# 09_-_MICROCONTROLLER_UNIT.net
KiCad netlist of a schematic drawn in Altium Designer
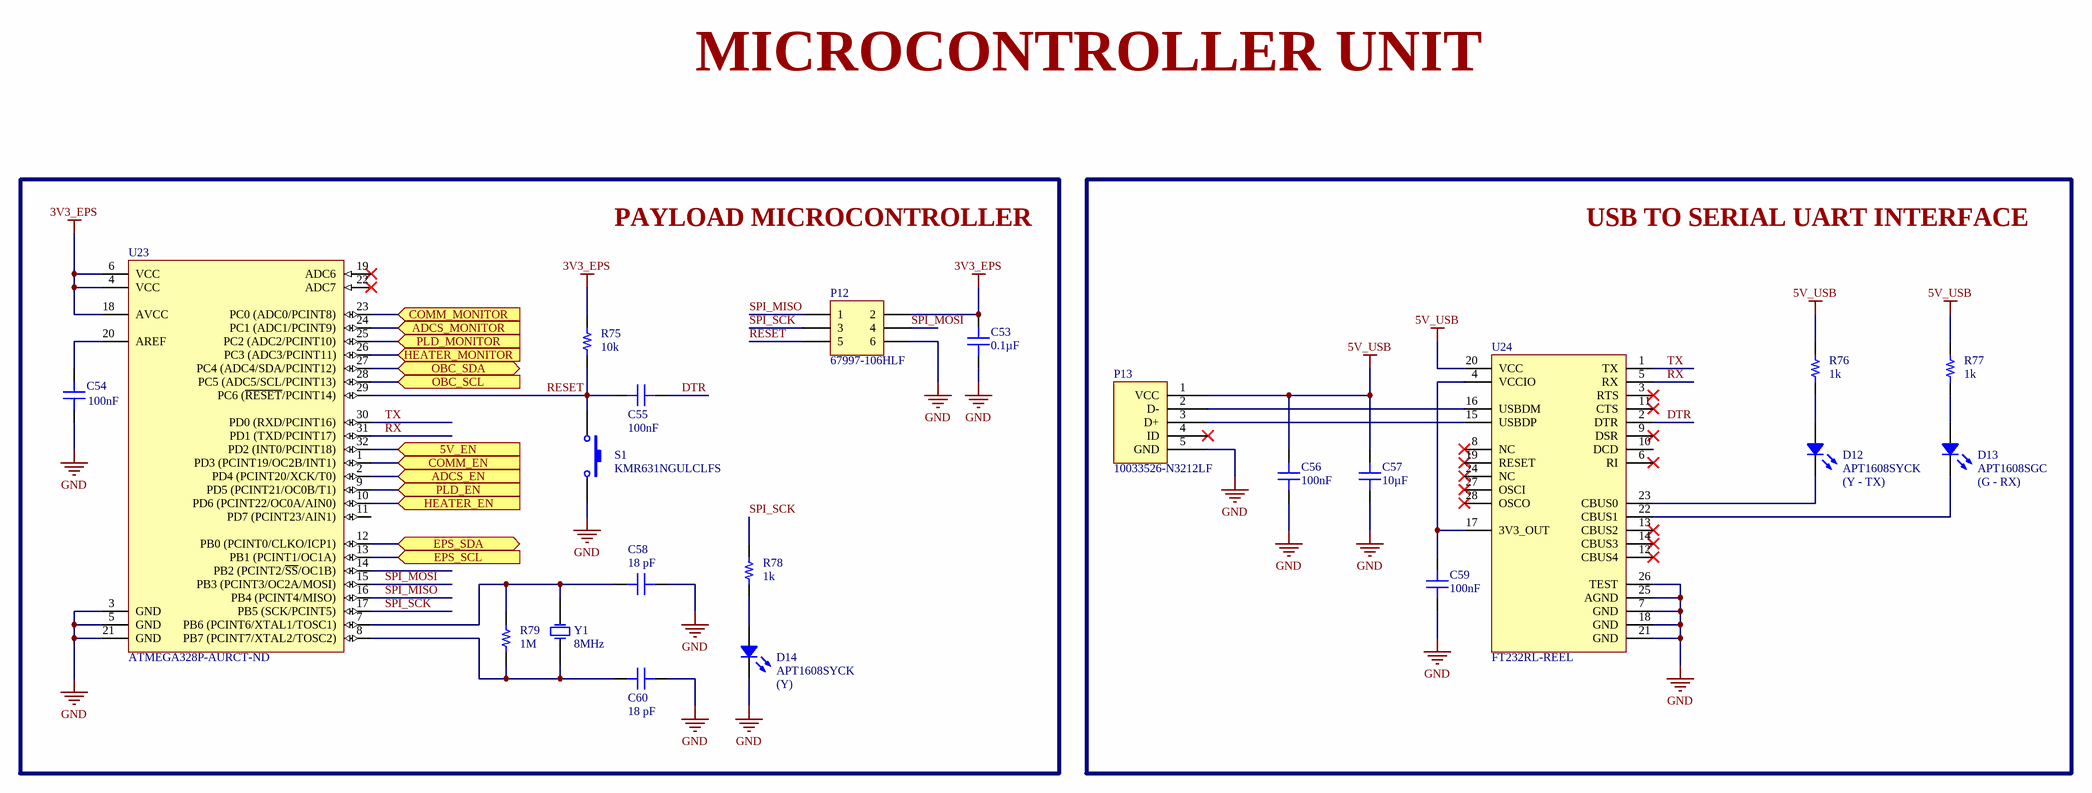
[diagram p0: [09] - MICROCONTROLLER UNIT.SchDoc]

(export (version "E")
  (design (tool "Eeschema 10.0.6"))
  (components
    (comp (ref "C53")
      (value "C2012X7R1H104K085AA")
      (footprint "CAP 0805/2012")
      (description "CAP CER 0.1UF 50V X7R 0805")
      (fields
        (field (name "MANUFACTURER") "TDK")
        (field (name "PCN PART NUMBER") "MLCC Part Number Change 30/Nov/2012")
        (field (name "CAPACITANCE") "0.1µF")
      )
      (libsource (lib "UVG") (part "C2012X7R1H104K085AA"))
    )
    (comp (ref "C54")
      (value "C0603C104K8RACTU")
      (footprint "CAP 0603/1608")
      (description "CAP CER 0.1UF 10V X7R 0603")
      (fields
        (field (name "MANUFACTURER") "KEMET")
        (field (name "CAPACITANCE") "100nF")
        (field (name "TOLERANCE") "10%")
      )
      (libsource (lib "UVG") (part "C0603C104K8RACTU"))
    )
    (comp (ref "C55")
      (value "C0603C104K8RACTU")
      (footprint "CAP 0603/1608")
      (description "CAP CER 0.1UF 10V X7R 0603")
      (fields
        (field (name "MANUFACTURER") "KEMET")
        (field (name "CAPACITANCE") "100nF")
        (field (name "TOLERANCE") "10%")
      )
      (libsource (lib "UVG") (part "C0603C104K8RACTU"))
    )
    (comp (ref "C56")
      (value "C0603C104K8RACTU")
      (footprint "CAP 0603/1608")
      (description "CAP CER 0.1UF 10V X7R 0603")
      (fields
        (field (name "MANUFACTURER") "KEMET")
        (field (name "CAPACITANCE") "100nF")
        (field (name "TOLERANCE") "10%")
      )
      (libsource (lib "UVG") (part "C0603C104K8RACTU"))
    )
    (comp (ref "C57")
      (value "LMK212BJ106KG-T")
      (footprint "CAP 0805/2012")
      (description "CAP CER 10UF 10V X5R 0805")
      (fields
        (field (name "MANUFACTURER") "Taiyo Yuden")
        (field (name "PCN PART NUMBER") "X5R, X7R Dielectrics 23/Jan/2008")
        (field (name "CAPACITANCE") "10µF")
      )
      (libsource (lib "UVG") (part "LMK212BJ106KG-T"))
    )
    (comp (ref "C58")
      (value "C0805C180J5GAC-TU")
      (footprint "CAP 0805/2012")
      (description "CAP CER 18PF 50V C0G/NP0 0805")
      (fields
        (field (name "MANUFACTURER") "KEMET")
        (field (name "CAPACITANCE") "18 pF")
        (field (name "VOLTAGE") "50VDC")
      )
      (libsource (lib "UVG") (part "C0805C180J5GAC-TU"))
    )
    (comp (ref "C59")
      (value "C0603C104K8RACTU")
      (footprint "CAP 0603/1608")
      (description "CAP CER 0.1UF 10V X7R 0603")
      (fields
        (field (name "MANUFACTURER") "KEMET")
        (field (name "CAPACITANCE") "100nF")
        (field (name "TOLERANCE") "10%")
      )
      (libsource (lib "UVG") (part "C0603C104K8RACTU"))
    )
    (comp (ref "C60")
      (value "C0805C180J5GAC-TU")
      (footprint "CAP 0805/2012")
      (description "CAP CER 18PF 50V C0G/NP0 0805")
      (fields
        (field (name "MANUFACTURER") "KEMET")
        (field (name "CAPACITANCE") "18 pF")
        (field (name "VOLTAGE") "50VDC")
      )
      (libsource (lib "UVG") (part "C0805C180J5GAC-TU"))
    )
    (comp (ref "D12")
      (value "APT1608SYCK")
      (footprint "LED 0603/1608 YELLOW")
      (description "LED YELLOW CLEAR CHIP SMD")
      (fields (field (name "MANUFACTURER") "Kingbright"))
      (libsource (lib "UVG") (part "APT1608SYCK"))
    )
    (comp (ref "D13")
      (value "APT1608SGC")
      (footprint "LED 0603/1608 GREEN")
      (description "LED 1.6X0.8MM 568NM GRN CLR SMD")
      (fields (field (name "MANUFACTURER") "Kingbright"))
      (libsource (lib "UVG") (part "APT1608SGC"))
    )
    (comp (ref "D14")
      (value "APT1608SYCK")
      (footprint "LED 0603/1608 YELLOW")
      (description "LED YELLOW CLEAR CHIP SMD")
      (fields (field (name "MANUFACTURER") "Kingbright"))
      (libsource (lib "UVG") (part "APT1608SYCK"))
    )
    (comp (ref "P12")
      (value "67997-106HLF")
      (footprint "67997-106HLF")
      (description "CONN HEADER 6POS .100 STR 30AU")
      (fields (field (name "MANUFACTURER") "Amphenol FCI"))
      (libsource (lib "UVG") (part "67997-106HLF"))
    )
    (comp (ref "P13")
      (value "10033526-N3212LF")
      (footprint "FCI USB 10033526-N3212LF")
      (description "CONN MINI USB RCPT RA TYPE B SMD")
      (fields (field (name "MANUFACTURER") "Amphenol FCI"))
      (libsource (lib "UVG") (part "10033526-N3212LF"))
    )
    (comp (ref "R75")
      (value "RNCP0603FTD10K0")
      (footprint "RES 0603/1608")
      (description "RES SMD 10K OHM 1% 1/8W 0603")
      (fields
        (field (name "MANUFACTURER") "Stackpole Electronics")
        (field (name "RESISTANCE") "10k")
        (field (name "TOLERANCE") "1%")
      )
      (libsource (lib "UVG") (part "RNCP0603FTD10K0"))
    )
    (comp (ref "R76")
      (value "ESR03EZPJ102")
      (footprint "RES 0603/1608")
      (description "RES SMD 1K OHM 5% 1/4W 0603")
      (fields
        (field (name "MANUFACTURER") "Rohm")
        (field (name "RESISTANCE") "1k")
        (field (name "TOLERANCE") "5%")
      )
      (libsource (lib "UVG") (part "ESR03EZPJ102"))
    )
    (comp (ref "R77")
      (value "ESR03EZPJ102")
      (footprint "RES 0603/1608")
      (description "RES SMD 1K OHM 5% 1/4W 0603")
      (fields
        (field (name "MANUFACTURER") "Rohm")
        (field (name "RESISTANCE") "1k")
        (field (name "TOLERANCE") "5%")
      )
      (libsource (lib "UVG") (part "ESR03EZPJ102"))
    )
    (comp (ref "R78")
      (value "ESR03EZPJ102")
      (footprint "RES 0603/1608")
      (description "RES SMD 1K OHM 5% 1/4W 0603")
      (fields
        (field (name "MANUFACTURER") "Rohm")
        (field (name "RESISTANCE") "1k")
        (field (name "TOLERANCE") "5%")
      )
      (libsource (lib "UVG") (part "ESR03EZPJ102"))
    )
    (comp (ref "R79")
      (value "RT0805FRE071ML")
      (footprint "RES 0805/2012")
      (description "RES SMD 1M OHM 1% 1/8W 0805")
      (fields
        (field (name "MANUFACTURER") "Yageo")
        (field (name "RESISTANCE") "1M")
        (field (name "TOLERANCE") "1%")
      )
      (libsource (lib "UVG") (part "RT0805FRE071ML"))
    )
    (comp (ref "S1")
      (value "KMR631NGULCLFS")
      (footprint "KMR631NGLFS")
      (description "SWITCH TACTILE SPST-NO 50MA 32V")
      (fields (field (name "MANUFACTURER") "ITT C&K"))
      (libsource (lib "UVG") (part "KMR631NGULCLFS"))
    )
    (comp (ref "U23")
      (value "ATMEGA328P-AURCT-ND")
      (footprint "32A_L")
      (description "IC MCU 8BIT 32KB FLASH 32TQFP")
      (fields
        (field (name "MANUFACTURER") "Microchip / Atmel")
        (field (name "MANUFACTURER PART NUMBER") "ATMEGA328P-AUR")
      )
      (libsource (lib "UVG") (part "ATMEGA328P-AUR"))
    )
    (comp (ref "U24")
      (value "FT232RL-REEL")
      (footprint "SOP65P790X200-28N")
      (description "IC USB FS SERIAL UART 28-SSOP")
      (fields (field (name "MANUFACTURER") "FTDI") (field (name "VOLTAGE") "5V"))
      (libsource (lib "UVG") (part "FT232RL-REEL"))
    )
    (comp (ref "Y1")
      (value "535-9831-1-ND")
      (footprint "ABM7")
      (description "CRYSTAL 8.0000MHZ 18PF SMD")
      (fields
        (field (name "MANUFACTURER") "Abracon")
        (field (name "MANUFACTURER PART NUMBER") "ABM7-8.000MHZ-D2Y-T")
        (field (name "FREQUENCY") "8MHz")
      )
      (libsource (lib "UVG") (part "535-9831-1-ND"))
    )
  )
  (nets
    (net (code "1") (name "/5V_EN") (class "Default")
      (node (ref "U23") (pin "32") (pinfunction "PD2_(INT0/PCINT18)_32") (pintype "bidirectional"))
    )
    (net (code "2") (name "/ADCS_EN") (class "Default")
      (node (ref "U23") (pin "2") (pinfunction "PD4_(PCINT20/XCK/T0)_2") (pintype "bidirectional"))
    )
    (net (code "3") (name "/ADCS_MONITOR") (class "Default")
      (node (ref "U23") (pin "24") (pinfunction "PC1_(ADC1/PCINT9)_24") (pintype "bidirectional"))
    )
    (net (code "4") (name "/COMM_EN") (class "Default")
      (node (ref "U23") (pin "1") (pinfunction "PD3_(PCINT19/OC2B/INT1)_1") (pintype "bidirectional"))
    )
    (net (code "5") (name "/COMM_MONITOR") (class "Default")
      (node (ref "U23") (pin "23") (pinfunction "PC0_(ADC0/PCINT8)_23") (pintype "bidirectional"))
    )
    (net (code "6") (name "/DTR") (class "Default")
      (node (ref "C55") (pin "1") (pinfunction "1_1") (pintype "passive"))
      (node (ref "U24") (pin "2") (pinfunction "DTR_2") (pintype "passive"))
    )
    (net (code "7") (name "/EPS_SCL") (class "Default")
      (node (ref "U23") (pin "13") (pinfunction "PB1_(PCINT1/OC1A)_13") (pintype "bidirectional"))
    )
    (net (code "8") (name "/EPS_SDA") (class "Default")
      (node (ref "U23") (pin "12") (pinfunction "PB0_(PCINT0/CLKO/ICP1)_12") (pintype "bidirectional"))
    )
    (net (code "9") (name "/HEATER_EN") (class "Default")
      (node (ref "U23") (pin "10") (pinfunction "PD6_(PCINT22/OC0A/AIN0)_10") (pintype "bidirectional"))
    )
    (net (code "10") (name "/HEATER_MONITOR") (class "Default")
      (node (ref "U23") (pin "26") (pinfunction "PC3_(ADC3/PCINT11)_26") (pintype "bidirectional"))
    )
    (net (code "11") (name "/OBC_SCL") (class "Default")
      (node (ref "U23") (pin "28") (pinfunction "PC5_(ADC5/SCL/PCINT13)_28") (pintype "bidirectional"))
    )
    (net (code "12") (name "/OBC_SDA") (class "Default")
      (node (ref "U23") (pin "27") (pinfunction "PC4_(ADC4/SDA/PCINT12)_27") (pintype "bidirectional"))
    )
    (net (code "13") (name "/PLD_EN") (class "Default")
      (node (ref "U23") (pin "9") (pinfunction "PD5_(PCINT21/OC0B/T1)_9") (pintype "bidirectional"))
    )
    (net (code "14") (name "/PLD_MONITOR") (class "Default")
      (node (ref "U23") (pin "25") (pinfunction "PC2_(ADC2/PCINT10)_25") (pintype "bidirectional"))
    )
    (net (code "15") (name "/RESET") (class "Default")
      (node (ref "C55") (pin "2") (pinfunction "2_2") (pintype "passive"))
      (node (ref "P12") (pin "5") (pinfunction "5_5") (pintype "passive"))
      (node (ref "R75") (pin "1") (pinfunction "1_1") (pintype "passive"))
      (node (ref "S1") (pin "1") (pinfunction "1_1") (pintype "passive"))
      (node (ref "U23") (pin "29") (pinfunction "PC6_(~{RESET}/PCINT14)_29") (pintype "bidirectional"))
    )
    (net (code "16") (name "/RX") (class "Default")
      (node (ref "U23") (pin "31") (pinfunction "PD1_(TXD/PCINT17)_31") (pintype "bidirectional"))
      (node (ref "U24") (pin "5") (pinfunction "RX_5") (pintype "passive"))
    )
    (net (code "17") (name "/SPI_MISO") (class "Default")
      (node (ref "P12") (pin "1") (pinfunction "1_1") (pintype "passive"))
      (node (ref "U23") (pin "16") (pinfunction "PB4_(PCINT4/MISO)_16") (pintype "bidirectional"))
    )
    (net (code "18") (name "/SPI_MOSI") (class "Default")
      (node (ref "P12") (pin "4") (pinfunction "4_4") (pintype "passive"))
      (node (ref "U23") (pin "15") (pinfunction "PB3_(PCINT3/OC2A/MOSI)_15") (pintype "bidirectional"))
    )
    (net (code "19") (name "/SPI_SCK") (class "Default")
      (node (ref "P12") (pin "3") (pinfunction "3_3") (pintype "passive"))
      (node (ref "R78") (pin "2") (pinfunction "2_2") (pintype "passive"))
      (node (ref "U23") (pin "17") (pinfunction "PB5_(SCK/PCINT5)_17") (pintype "bidirectional"))
    )
    (net (code "20") (name "/TX") (class "Default")
      (node (ref "U23") (pin "30") (pinfunction "PD0_(RXD/PCINT16)_30") (pintype "bidirectional"))
      (node (ref "U24") (pin "1") (pinfunction "TX_1") (pintype "passive"))
    )
    (net (code "21") (name "3V3_EPS") (class "Default")
      (node (ref "C53") (pin "2") (pinfunction "2_2") (pintype "passive"))
      (node (ref "P12") (pin "2") (pinfunction "2_2") (pintype "passive"))
      (node (ref "R75") (pin "2") (pinfunction "2_2") (pintype "passive"))
      (node (ref "U23") (pin "18") (pinfunction "AVCC_18") (pintype "power_in"))
      (node (ref "U23") (pin "4") (pinfunction "VCC_4") (pintype "power_in"))
      (node (ref "U23") (pin "6") (pinfunction "VCC_6") (pintype "power_in"))
    )
    (net (code "22") (name "5V_USB") (class "Default")
      (node (ref "C56") (pin "1") (pinfunction "1_1") (pintype "passive"))
      (node (ref "C57") (pin "2") (pinfunction "2_2") (pintype "passive"))
      (node (ref "P13") (pin "1") (pinfunction "VCC_1") (pintype "passive"))
      (node (ref "R76") (pin "2") (pinfunction "2_2") (pintype "passive"))
      (node (ref "R77") (pin "2") (pinfunction "2_2") (pintype "passive"))
      (node (ref "U24") (pin "20") (pinfunction "VCC_20") (pintype "passive"))
    )
    (net (code "23") (name "GND") (class "Default")
      (node (ref "C53") (pin "1") (pinfunction "1_1") (pintype "passive"))
      (node (ref "C54") (pin "1") (pinfunction "1_1") (pintype "passive"))
      (node (ref "C56") (pin "2") (pinfunction "2_2") (pintype "passive"))
      (node (ref "C57") (pin "1") (pinfunction "1_1") (pintype "passive"))
      (node (ref "C58") (pin "2") (pinfunction "2_2") (pintype "passive"))
      (node (ref "C59") (pin "2") (pinfunction "2_2") (pintype "passive"))
      (node (ref "C60") (pin "2") (pinfunction "2_2") (pintype "passive"))
      (node (ref "D14") (pin "2") (pinfunction "2_2") (pintype "passive"))
      (node (ref "P12") (pin "6") (pinfunction "6_6") (pintype "passive"))
      (node (ref "P13") (pin "5") (pinfunction "GND_5") (pintype "passive"))
      (node (ref "S1") (pin "2") (pinfunction "2_2") (pintype "passive"))
      (node (ref "U23") (pin "21") (pinfunction "GND_21") (pintype "power_in"))
      (node (ref "U23") (pin "3") (pinfunction "GND_3") (pintype "power_in"))
      (node (ref "U23") (pin "5") (pinfunction "GND_5") (pintype "power_in"))
      (node (ref "U24") (pin "18") (pinfunction "GND_18") (pintype "passive"))
      (node (ref "U24") (pin "21") (pinfunction "GND_21") (pintype "passive"))
      (node (ref "U24") (pin "25") (pinfunction "AGND_25") (pintype "passive"))
      (node (ref "U24") (pin "26") (pinfunction "TEST_26") (pintype "passive"))
      (node (ref "U24") (pin "7") (pinfunction "GND_7") (pintype "passive"))
    )
    (net (code "24") (name "Net-(D12-Pad1)") (class "Default")
      (node (ref "D12") (pin "1") (pinfunction "1_1") (pintype "passive"))
      (node (ref "R76") (pin "1") (pinfunction "1_1") (pintype "passive"))
    )
    (net (code "25") (name "Net-(D13-Pad1)") (class "Default")
      (node (ref "D13") (pin "1") (pinfunction "1_1") (pintype "passive"))
      (node (ref "R77") (pin "1") (pinfunction "1_1") (pintype "passive"))
    )
    (net (code "26") (name "Net-(D14-Pad1)") (class "Default")
      (node (ref "D14") (pin "1") (pinfunction "1_1") (pintype "passive"))
      (node (ref "R78") (pin "1") (pinfunction "1_1") (pintype "passive"))
    )
    (net (code "27") (name "Net-(P13-D+)") (class "Default")
      (node (ref "P13") (pin "3") (pinfunction "D+_3") (pintype "passive"))
      (node (ref "U24") (pin "15") (pinfunction "USBDP_15") (pintype "passive"))
    )
    (net (code "28") (name "Net-(P13-D-)") (class "Default")
      (node (ref "P13") (pin "2") (pinfunction "D-_2") (pintype "passive"))
      (node (ref "U24") (pin "16") (pinfunction "USBDM_16") (pintype "passive"))
    )
    (net (code "29") (name "Net-(U23-AREF)") (class "Default")
      (node (ref "C54") (pin "2") (pinfunction "2_2") (pintype "passive"))
      (node (ref "U23") (pin "20") (pinfunction "AREF_20") (pintype "passive"))
    )
    (net (code "30") (name "Net-(U23-PB6_(PCINT6{slash}XTAL1{slash}TOSC1))") (class "Default")
      (node (ref "C58") (pin "1") (pinfunction "1_1") (pintype "passive"))
      (node (ref "R79") (pin "1") (pinfunction "1_1") (pintype "passive"))
      (node (ref "U23") (pin "7") (pinfunction "PB6_(PCINT6/XTAL1/TOSC1)_7") (pintype "bidirectional"))
      (node (ref "Y1") (pin "2") (pinfunction "OSC2_2") (pintype "passive"))
    )
    (net (code "31") (name "Net-(U23-PB7_(PCINT7{slash}XTAL2{slash}TOSC2))") (class "Default")
      (node (ref "C60") (pin "1") (pinfunction "1_1") (pintype "passive"))
      (node (ref "R79") (pin "2") (pinfunction "2_2") (pintype "passive"))
      (node (ref "U23") (pin "8") (pinfunction "PB7_(PCINT7/XTAL2/TOSC2)_8") (pintype "bidirectional"))
      (node (ref "Y1") (pin "1") (pinfunction "OSC1_1") (pintype "passive"))
    )
    (net (code "32") (name "Net-(U24-3V3_OUT)") (class "Default")
      (node (ref "C59") (pin "1") (pinfunction "1_1") (pintype "passive"))
      (node (ref "U24") (pin "17") (pinfunction "3V3_OUT_17") (pintype "passive"))
      (node (ref "U24") (pin "4") (pinfunction "VCCIO_4") (pintype "passive"))
    )
    (net (code "33") (name "Net-(U24-CBUS0)") (class "Default")
      (node (ref "D12") (pin "2") (pinfunction "2_2") (pintype "passive"))
      (node (ref "U24") (pin "23") (pinfunction "CBUS0_23") (pintype "passive"))
    )
    (net (code "34") (name "Net-(U24-CBUS1)") (class "Default")
      (node (ref "D13") (pin "2") (pinfunction "2_2") (pintype "passive"))
      (node (ref "U24") (pin "22") (pinfunction "CBUS1_22") (pintype "passive"))
    )
    (net (code "35") (name "unconnected-(P13-ID-Pad4)") (class "Default")
      (node (ref "P13") (pin "4") (pinfunction "ID_4") (pintype "passive+no_connect"))
    )
    (net (code "36") (name "unconnected-(U23-ADC6-Pad19)") (class "Default")
      (node (ref "U23") (pin "19") (pinfunction "ADC6_19") (pintype "input+no_connect"))
    )
    (net (code "37") (name "unconnected-(U23-ADC7-Pad22)") (class "Default")
      (node (ref "U23") (pin "22") (pinfunction "ADC7_22") (pintype "input+no_connect"))
    )
    (net (code "38") (name "unconnected-(U23-PB2_(PCINT2{slash}~{SS}{slash}OC1B)-Pad14)") (class "Default")
      (node (ref "U23") (pin "14") (pinfunction "PB2_(PCINT2/~{SS}/OC1B)_14") (pintype "bidirectional"))
    )
    (net (code "39") (name "unconnected-(U23-PD7_(PCINT23{slash}AIN1)-Pad11)") (class "Default")
      (node (ref "U23") (pin "11") (pinfunction "PD7_(PCINT23/AIN1)_11") (pintype "bidirectional"))
    )
    (net (code "40") (name "unconnected-(U24-CBUS2-Pad13)") (class "Default")
      (node (ref "U24") (pin "13") (pinfunction "CBUS2_13") (pintype "passive+no_connect"))
    )
    (net (code "41") (name "unconnected-(U24-CBUS3-Pad14)") (class "Default")
      (node (ref "U24") (pin "14") (pinfunction "CBUS3_14") (pintype "passive+no_connect"))
    )
    (net (code "42") (name "unconnected-(U24-CBUS4-Pad12)") (class "Default")
      (node (ref "U24") (pin "12") (pinfunction "CBUS4_12") (pintype "passive+no_connect"))
    )
    (net (code "43") (name "unconnected-(U24-CTS-Pad11)") (class "Default")
      (node (ref "U24") (pin "11") (pinfunction "CTS_11") (pintype "passive+no_connect"))
    )
    (net (code "44") (name "unconnected-(U24-DCD-Pad10)") (class "Default")
      (node (ref "U24") (pin "10") (pinfunction "DCD_10") (pintype "passive"))
    )
    (net (code "45") (name "unconnected-(U24-DSR-Pad9)") (class "Default")
      (node (ref "U24") (pin "9") (pinfunction "DSR_9") (pintype "passive+no_connect"))
    )
    (net (code "46") (name "unconnected-(U24-NC-Pad8)") (class "Default")
      (node (ref "U24") (pin "8") (pinfunction "NC_8") (pintype "passive+no_connect"))
    )
    (net (code "47") (name "unconnected-(U24-NC-Pad24)") (class "Default")
      (node (ref "U24") (pin "24") (pinfunction "NC_24") (pintype "passive+no_connect"))
    )
    (net (code "48") (name "unconnected-(U24-OSCI-Pad27)") (class "Default")
      (node (ref "U24") (pin "27") (pinfunction "OSCI_27") (pintype "passive+no_connect"))
    )
    (net (code "49") (name "unconnected-(U24-OSCO-Pad28)") (class "Default")
      (node (ref "U24") (pin "28") (pinfunction "OSCO_28") (pintype "passive+no_connect"))
    )
    (net (code "50") (name "unconnected-(U24-RESET-Pad19)") (class "Default")
      (node (ref "U24") (pin "19") (pinfunction "RESET_19") (pintype "passive+no_connect"))
    )
    (net (code "51") (name "unconnected-(U24-RI-Pad6)") (class "Default")
      (node (ref "U24") (pin "6") (pinfunction "RI_6") (pintype "passive+no_connect"))
    )
    (net (code "52") (name "unconnected-(U24-RTS-Pad3)") (class "Default")
      (node (ref "U24") (pin "3") (pinfunction "RTS_3") (pintype "passive+no_connect"))
    )
  )
)
